# SPI_Devices.net
KiCad netlist of a schematic drawn in Altium Designer
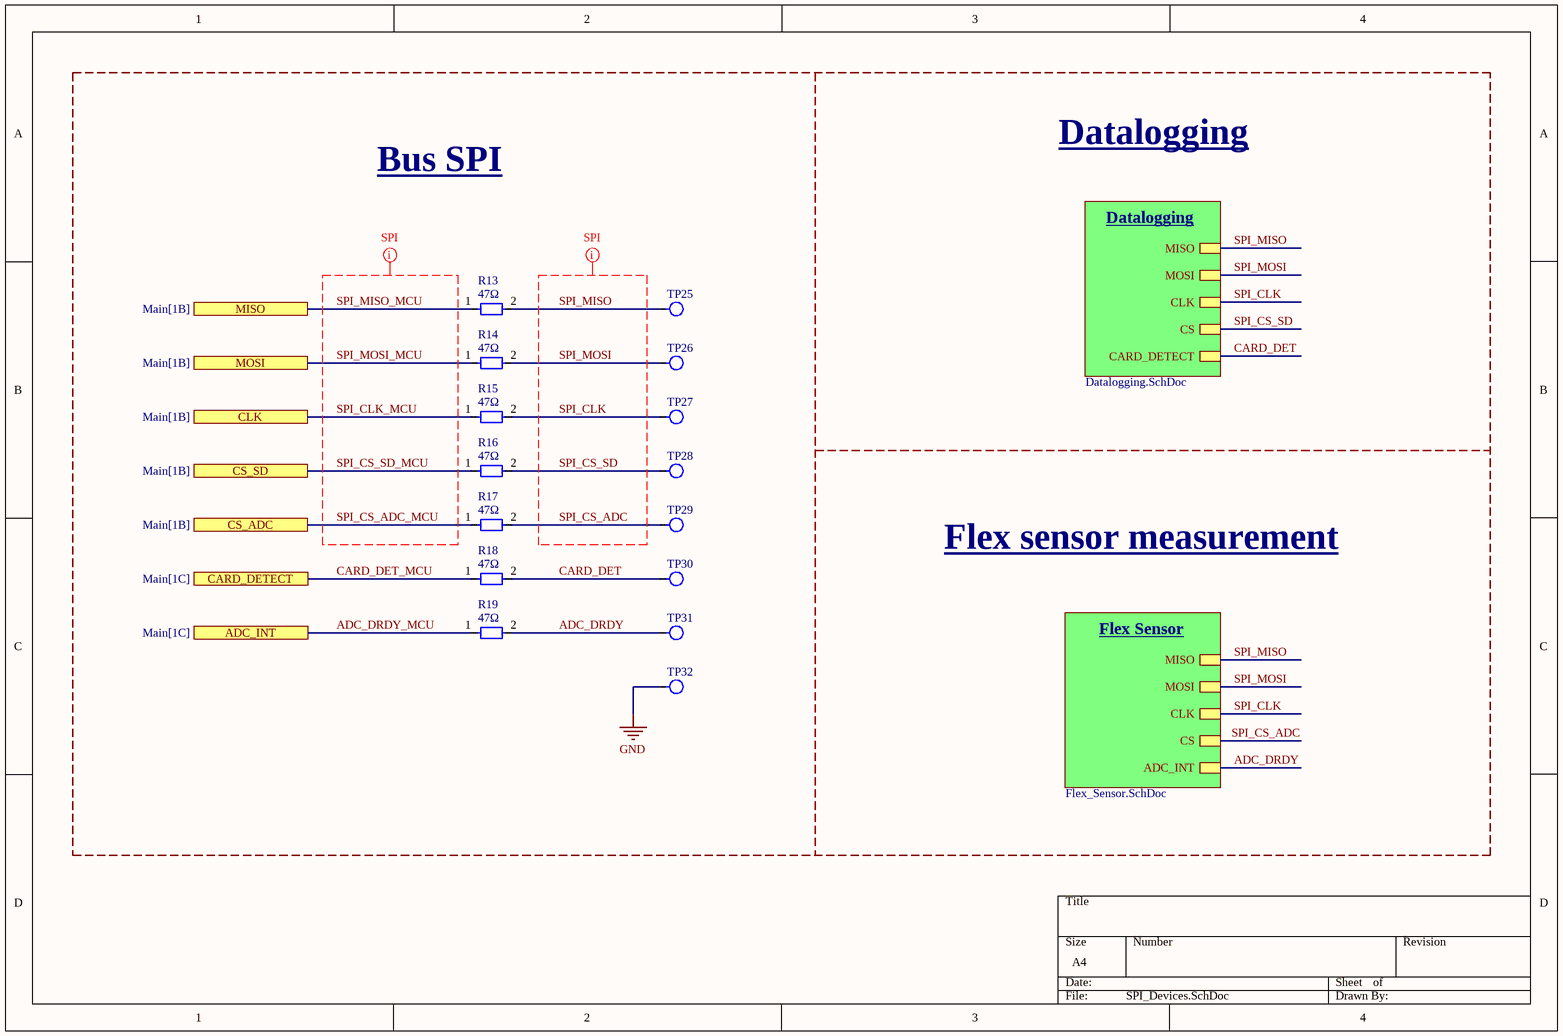
[diagram p0: SPI_Devices.SchDoc]

(export (version "E")
  (design (tool "Eeschema 10.0.6"))
  (components
    (comp (ref "R13")
      (value "47Ω")
      (footprint "RES_0603")
      (description "RES  47R 1% 0603")
      (fields (field (name "Comment") "47R"))
      (libsource (lib "Passive_Components") (part "Generic R"))
    )
    (comp (ref "R14")
      (value "47Ω")
      (footprint "RES_0603")
      (description "RES  47R 1% 0603")
      (fields (field (name "Comment") "47R"))
      (libsource (lib "Passive_Components") (part "Generic R"))
    )
    (comp (ref "R15")
      (value "47Ω")
      (footprint "RES_0603")
      (description "RES  47R 1% 0603")
      (fields (field (name "Comment") "47R"))
      (libsource (lib "Passive_Components") (part "Generic R"))
    )
    (comp (ref "R16")
      (value "47Ω")
      (footprint "RES_0603")
      (description "RES  47R 1% 0603")
      (fields (field (name "Comment") "47R"))
      (libsource (lib "Passive_Components") (part "Generic R"))
    )
    (comp (ref "R17")
      (value "47Ω")
      (footprint "RES_0603")
      (description "RES  47R 1% 0603")
      (fields (field (name "Comment") "47R"))
      (libsource (lib "Passive_Components") (part "Generic R"))
    )
    (comp (ref "R18")
      (value "47Ω")
      (footprint "RES_0603")
      (description "RES  47R 1% 0603")
      (fields (field (name "Comment") "47R"))
      (libsource (lib "Passive_Components") (part "Generic R"))
    )
    (comp (ref "R19")
      (value "47Ω")
      (footprint "RES_0603")
      (description "RES  47R 1% 0603")
      (fields (field (name "Comment") "47R"))
      (libsource (lib "Passive_Components") (part "Generic R"))
    )
    (comp (ref "TP25")
      (value "Testpoint SMD")
      (footprint "Testpoint_SMD")
      (description "Testpoint SMD de 1mm de diametro.")
      (libsource (lib "Connectors") (part "Testpoint_SMD"))
    )
    (comp (ref "TP26")
      (value "Testpoint SMD")
      (footprint "Testpoint_SMD")
      (description "Testpoint SMD de 1mm de diametro.")
      (libsource (lib "Connectors") (part "Testpoint_SMD"))
    )
    (comp (ref "TP27")
      (value "Testpoint SMD")
      (footprint "Testpoint_SMD")
      (description "Testpoint SMD de 1mm de diametro.")
      (libsource (lib "Connectors") (part "Testpoint_SMD"))
    )
    (comp (ref "TP28")
      (value "Testpoint SMD")
      (footprint "Testpoint_SMD")
      (description "Testpoint SMD de 1mm de diametro.")
      (libsource (lib "Connectors") (part "Testpoint_SMD"))
    )
    (comp (ref "TP29")
      (value "Testpoint SMD")
      (footprint "Testpoint_SMD")
      (description "Testpoint SMD de 1mm de diametro.")
      (libsource (lib "Connectors") (part "Testpoint_SMD"))
    )
    (comp (ref "TP30")
      (value "Testpoint SMD")
      (footprint "Testpoint_SMD")
      (description "Testpoint SMD de 1mm de diametro.")
      (libsource (lib "Connectors") (part "Testpoint_SMD"))
    )
    (comp (ref "TP31")
      (value "Testpoint SMD")
      (footprint "Testpoint_SMD")
      (description "Testpoint SMD de 1mm de diametro.")
      (libsource (lib "Connectors") (part "Testpoint_SMD"))
    )
    (comp (ref "TP32")
      (value "Testpoint SMD")
      (footprint "Testpoint_SMD")
      (description "Testpoint SMD de 1mm de diametro.")
      (libsource (lib "Connectors") (part "Testpoint_SMD"))
    )
  )
  (nets
    (net (code "1") (name "/ADC_DRDY") (class "Default")
      (node (ref "R19") (pin "2") (pinfunction "2_2") (pintype "passive"))
      (node (ref "TP31") (pin "1") (pinfunction "1_1") (pintype "passive"))
    )
    (net (code "2") (name "/ADC_DRDY_MCU") (class "Default")
      (node (ref "R19") (pin "1") (pinfunction "1_1") (pintype "passive"))
    )
    (net (code "3") (name "/CARD_DET") (class "Default")
      (node (ref "R18") (pin "2") (pinfunction "2_2") (pintype "passive"))
      (node (ref "TP30") (pin "1") (pinfunction "1_1") (pintype "passive"))
    )
    (net (code "4") (name "/CARD_DET_MCU") (class "Default")
      (node (ref "R18") (pin "1") (pinfunction "1_1") (pintype "passive"))
    )
    (net (code "5") (name "/SPI_CLK") (class "Default")
      (node (ref "R15") (pin "2") (pinfunction "2_2") (pintype "passive"))
      (node (ref "TP27") (pin "1") (pinfunction "1_1") (pintype "passive"))
    )
    (net (code "6") (name "/SPI_CLK_MCU") (class "Default")
      (node (ref "R15") (pin "1") (pinfunction "1_1") (pintype "passive"))
    )
    (net (code "7") (name "/SPI_CS_ADC") (class "Default")
      (node (ref "R17") (pin "2") (pinfunction "2_2") (pintype "passive"))
      (node (ref "TP29") (pin "1") (pinfunction "1_1") (pintype "passive"))
    )
    (net (code "8") (name "/SPI_CS_ADC_MCU") (class "Default")
      (node (ref "R17") (pin "1") (pinfunction "1_1") (pintype "passive"))
    )
    (net (code "9") (name "/SPI_CS_SD") (class "Default")
      (node (ref "R16") (pin "2") (pinfunction "2_2") (pintype "passive"))
      (node (ref "TP28") (pin "1") (pinfunction "1_1") (pintype "passive"))
    )
    (net (code "10") (name "/SPI_CS_SD_MCU") (class "Default")
      (node (ref "R16") (pin "1") (pinfunction "1_1") (pintype "passive"))
    )
    (net (code "11") (name "/SPI_MISO") (class "Default")
      (node (ref "R13") (pin "2") (pinfunction "2_2") (pintype "passive"))
      (node (ref "TP25") (pin "1") (pinfunction "1_1") (pintype "passive"))
    )
    (net (code "12") (name "/SPI_MISO_MCU") (class "Default")
      (node (ref "R13") (pin "1") (pinfunction "1_1") (pintype "passive"))
    )
    (net (code "13") (name "/SPI_MOSI") (class "Default")
      (node (ref "R14") (pin "2") (pinfunction "2_2") (pintype "passive"))
      (node (ref "TP26") (pin "1") (pinfunction "1_1") (pintype "passive"))
    )
    (net (code "14") (name "/SPI_MOSI_MCU") (class "Default")
      (node (ref "R14") (pin "1") (pinfunction "1_1") (pintype "passive"))
    )
    (net (code "15") (name "GND") (class "Default")
      (node (ref "TP32") (pin "1") (pinfunction "1_1") (pintype "passive"))
    )
  )
)
